# 2211B_SysArrosage_auto.net
KiCad netlist of a schematic drawn in Altium Designer
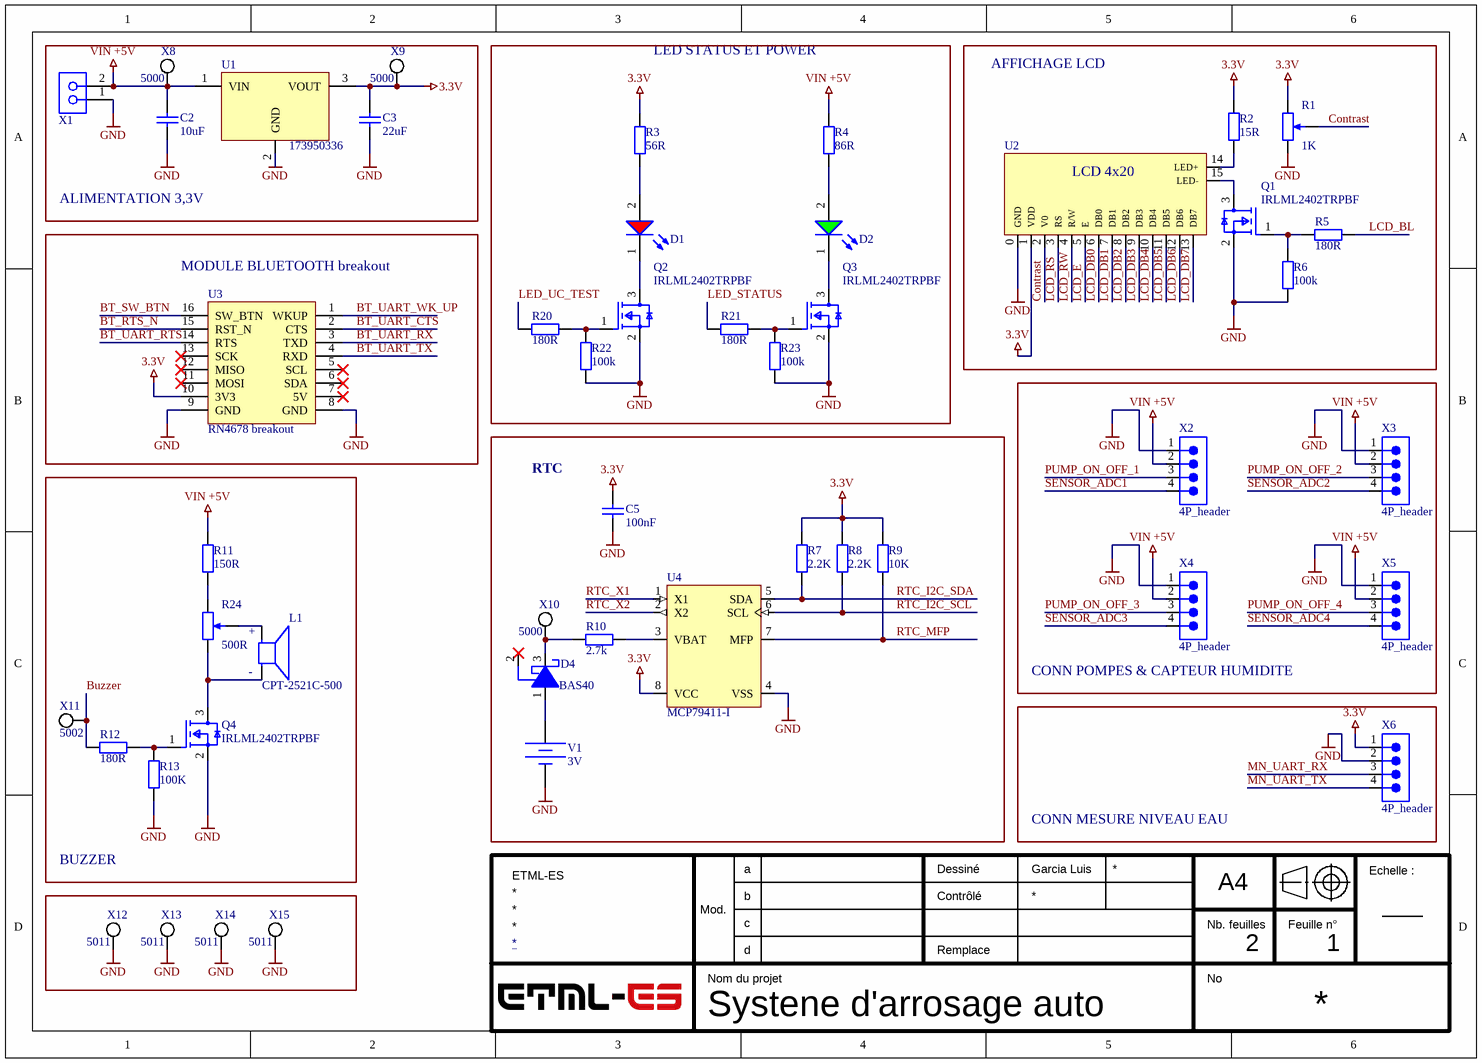
[diagram p0: 2211B_SysArrosage_auto.SchDoc]

(export (version "E")
  (design (tool "Eeschema 10.0.6"))
  (components
    (comp (ref "C2")
      (value "10uF")
      (footprint "CAPC2013X145X48NL20T23")
      (libsource (lib "Sys_Arossage") (part "Capacitor_Non-Polarized"))
    )
    (comp (ref "C3")
      (value "22uF")
      (footprint "CAPC2013X145X48NL20T23")
      (libsource (lib "Sys_Arossage") (part "Capacitor_Non-Polarized"))
    )
    (comp (ref "C5")
      (value "100nF")
      (footprint "CAPC2013X145X48NL20T23")
      (libsource (lib "Sys_Arossage") (part "Capacitor_Non-Polarized"))
    )
    (comp (ref "D1")
      (value "LED_Red_2A-1K")
      (description "LED Uni-Color Hyper Red 640nm 2-Pin Chip LED T/R")
      (fields
        (field (name "MANUFACTURER") "Kingbright")
        (field (name "MANUFACTURER PART NUMBER") "APT2012SECK/J3-PRV")
      )
      (libsource (lib "Optoelectronic") (part "LED_Red_2A-1K"))
    )
    (comp (ref "D2")
      (value "LED_Green_2A-1K")
      (description "LED Uni-Color Green 515nm 2-Pin SMD T/R")
      (fields
        (field (name "MANUFACTURER") "Kingbright")
        (field (name "MANUFACTURER PART NUMBER") "APHCM2012ZGCK-F01")
      )
      (libsource (lib "Optoelectronic") (part "LED_Green_2A-1K"))
    )
    (comp (ref "D4")
      (value "BAS40")
      (footprint "INF-SOT23_M")
      (description "Silicon Schottky Diode, -55 to 150 degC, SOT23, Reel, Green")
      (fields (field (name "MANUFACTURER") "Infineon"))
      (libsource (lib "Sys_Arossage") (part "CMP-1182-00023-1"))
    )
    (comp (ref "L1")
      (value "CPT-2521C-500")
      (description "AUDIO PIEZO TRANSDUCER 50V CHAS")
      (fields (field (name "MANUFACTURER") "CUI Devices"))
      (libsource (lib "Sys_Arossage") (part "Buzzer"))
    )
    (comp (ref "Q1")
      (value "IRLML2402TRPBF")
      (footprint "FP-Micro3-IPC_C")
      (description "MOSFET N-CH 20V 1.2A SOT-23")
      (fields (field (name "MANUFACTURER") "Infineon"))
      (libsource (lib "Sys_Arossage") (part "CMP-32901-000179-1"))
    )
    (comp (ref "Q2")
      (value "IRLML2402TRPBF")
      (footprint "FP-Micro3-IPC_C")
      (description "MOSFET N-CH 20V 1.2A SOT-23")
      (fields (field (name "MANUFACTURER") "Infineon"))
      (libsource (lib "Sys_Arossage") (part "CMP-32901-000179-1"))
    )
    (comp (ref "Q3")
      (value "IRLML2402TRPBF")
      (footprint "FP-Micro3-IPC_C")
      (description "MOSFET N-CH 20V 1.2A SOT-23")
      (fields (field (name "MANUFACTURER") "Infineon"))
      (libsource (lib "Sys_Arossage") (part "CMP-32901-000179-1"))
    )
    (comp (ref "Q4")
      (value "IRLML2402TRPBF")
      (footprint "FP-Micro3-IPC_C")
      (description "MOSFET N-CH 20V 1.2A SOT-23")
      (fields (field (name "MANUFACTURER") "Infineon"))
      (libsource (lib "Sys_Arossage") (part "CMP-32901-000179-1"))
    )
    (comp (ref "R1")
      (value "1K")
      (footprint "TRIM_3362P-1-102LF")
      (description "In a Tube of 50, 1kO Through Hole Trimmer Potentiometer 0.5W Top Adjust Bourns 3362 Series")
      (fields
        (field (name "MANUFACTURER") "Bourns")
        (field (name "MANUFACTURER PART NUMBER") "3362P-1-102LF")
        (field (name "PUBLISHER") "Altium Limited")
      )
      (libsource (lib "Sys_Arossage") (part "RPot"))
    )
    (comp (ref "R2")
      (value "15R")
      (footprint "RC0805N_YAG-M")
      (description "SMD Chip Resistor, 10 kOhm, ± 1%, 125 mW, 0805 [2012 Metric], Thick Film, General Purpose")
      (fields
        (field (name "MANUFACTURER") "Yageo")
        (field (name "MANUFACTURER PART NUMBER") "RC0805FR-0710KL")
      )
      (libsource (lib "") (part "R-SMD_1"))
    )
    (comp (ref "R3")
      (value "56R")
      (footprint "RC0805N_YAG-M")
      (description "SMD Chip Resistor, 10 kOhm, ± 1%, 125 mW, 0805 [2012 Metric], Thick Film, General Purpose")
      (fields
        (field (name "MANUFACTURER") "Yageo")
        (field (name "MANUFACTURER PART NUMBER") "RC0805FR-0710KL")
      )
      (libsource (lib "") (part "R-SMD_1"))
    )
    (comp (ref "R4")
      (value "86R")
      (footprint "RC0805N_YAG-M")
      (description "SMD Chip Resistor, 10 kOhm, ± 1%, 125 mW, 0805 [2012 Metric], Thick Film, General Purpose")
      (fields
        (field (name "MANUFACTURER") "Yageo")
        (field (name "MANUFACTURER PART NUMBER") "RC0805FR-0710KL")
      )
      (libsource (lib "") (part "R-SMD_1"))
    )
    (comp (ref "R5")
      (value "180R")
      (footprint "RC0805N_YAG-M")
      (description "SMD Chip Resistor, 10 kOhm, ± 1%, 125 mW, 0805 [2012 Metric], Thick Film, General Purpose")
      (fields
        (field (name "MANUFACTURER") "Yageo")
        (field (name "MANUFACTURER PART NUMBER") "RC0805FR-0710KL")
      )
      (libsource (lib "Sys_Arossage") (part "R-SMD"))
    )
    (comp (ref "R6")
      (value "100k")
      (footprint "RC0805N_YAG-M")
      (description "SMD Chip Resistor, 10 kOhm, ± 1%, 125 mW, 0805 [2012 Metric], Thick Film, General Purpose")
      (fields
        (field (name "MANUFACTURER") "Yageo")
        (field (name "MANUFACTURER PART NUMBER") "RC0805FR-0710KL")
      )
      (libsource (lib "") (part "R-SMD_1"))
    )
    (comp (ref "R7")
      (value "2.2K")
      (footprint "RC0805N_YAG-M")
      (description "SMD Chip Resistor, 10 kOhm, ± 1%, 125 mW, 0805 [2012 Metric], Thick Film, General Purpose")
      (fields
        (field (name "MANUFACTURER") "Yageo")
        (field (name "MANUFACTURER PART NUMBER") "RC0805FR-0710KL")
      )
      (libsource (lib "") (part "R-SMD_1"))
    )
    (comp (ref "R8")
      (value "2.2K")
      (footprint "RC0805N_YAG-M")
      (description "SMD Chip Resistor, 10 kOhm, ± 1%, 125 mW, 0805 [2012 Metric], Thick Film, General Purpose")
      (fields
        (field (name "MANUFACTURER") "Yageo")
        (field (name "MANUFACTURER PART NUMBER") "RC0805FR-0710KL")
      )
      (libsource (lib "") (part "R-SMD_1"))
    )
    (comp (ref "R9")
      (value "10K")
      (footprint "RC0805N_YAG-M")
      (description "SMD Chip Resistor, 10 kOhm, ± 1%, 125 mW, 0805 [2012 Metric], Thick Film, General Purpose")
      (fields
        (field (name "MANUFACTURER") "Yageo")
        (field (name "MANUFACTURER PART NUMBER") "RC0805FR-0710KL")
      )
      (libsource (lib "") (part "R-SMD_1"))
    )
    (comp (ref "R10")
      (value "2.7k")
      (footprint "RC0805N_YAG-M")
      (description "SMD Chip Resistor, 10 kOhm, ± 1%, 125 mW, 0805 [2012 Metric], Thick Film, General Purpose")
      (fields
        (field (name "MANUFACTURER") "Yageo")
        (field (name "MANUFACTURER PART NUMBER") "RC0805FR-0710KL")
      )
      (libsource (lib "Sys_Arossage") (part "R-SMD"))
    )
    (comp (ref "R11")
      (value "150R")
      (footprint "RC0805N_YAG-M")
      (description "SMD Chip Resistor, 10 kOhm, ± 1%, 125 mW, 0805 [2012 Metric], Thick Film, General Purpose")
      (fields
        (field (name "MANUFACTURER") "Yageo")
        (field (name "MANUFACTURER PART NUMBER") "RC0805FR-0710KL")
      )
      (libsource (lib "") (part "R-SMD_1"))
    )
    (comp (ref "R12")
      (value "180R")
      (footprint "RC0805N_YAG-M")
      (description "SMD Chip Resistor, 10 kOhm, ± 1%, 125 mW, 0805 [2012 Metric], Thick Film, General Purpose")
      (fields
        (field (name "MANUFACTURER") "Yageo")
        (field (name "MANUFACTURER PART NUMBER") "RC0805FR-0710KL")
      )
      (libsource (lib "Sys_Arossage") (part "R-SMD"))
    )
    (comp (ref "R13")
      (value "100K")
      (footprint "RC0805N_YAG-M")
      (description "SMD Chip Resistor, 10 kOhm, ± 1%, 125 mW, 0805 [2012 Metric], Thick Film, General Purpose")
      (fields
        (field (name "MANUFACTURER") "Yageo")
        (field (name "MANUFACTURER PART NUMBER") "RC0805FR-0710KL")
      )
      (libsource (lib "") (part "R-SMD_2"))
    )
    (comp (ref "R20")
      (value "180R")
      (footprint "RC0805N_YAG-M")
      (description "SMD Chip Resistor, 10 kOhm, ± 1%, 125 mW, 0805 [2012 Metric], Thick Film, General Purpose")
      (fields
        (field (name "MANUFACTURER") "Yageo")
        (field (name "MANUFACTURER PART NUMBER") "RC0805FR-0710KL")
      )
      (libsource (lib "Sys_Arossage") (part "R-SMD"))
    )
    (comp (ref "R21")
      (value "180R")
      (footprint "RC0805N_YAG-M")
      (description "SMD Chip Resistor, 10 kOhm, ± 1%, 125 mW, 0805 [2012 Metric], Thick Film, General Purpose")
      (fields
        (field (name "MANUFACTURER") "Yageo")
        (field (name "MANUFACTURER PART NUMBER") "RC0805FR-0710KL")
      )
      (libsource (lib "Sys_Arossage") (part "R-SMD"))
    )
    (comp (ref "R22")
      (value "100k")
      (footprint "RC0805N_YAG-M")
      (description "SMD Chip Resistor, 10 kOhm, ± 1%, 125 mW, 0805 [2012 Metric], Thick Film, General Purpose")
      (fields
        (field (name "MANUFACTURER") "Yageo")
        (field (name "MANUFACTURER PART NUMBER") "RC0805FR-0710KL")
      )
      (libsource (lib "") (part "R-SMD_1"))
    )
    (comp (ref "R23")
      (value "100k")
      (footprint "RC0805N_YAG-M")
      (description "SMD Chip Resistor, 10 kOhm, ± 1%, 125 mW, 0805 [2012 Metric], Thick Film, General Purpose")
      (fields
        (field (name "MANUFACTURER") "Yageo")
        (field (name "MANUFACTURER PART NUMBER") "RC0805FR-0710KL")
      )
      (libsource (lib "") (part "R-SMD_1"))
    )
    (comp (ref "R24")
      (value "500R")
      (footprint "TRIM_3362P-1-102LF")
      (description "In a Tube of 50, 1kO Through Hole Trimmer Potentiometer 0.5W Top Adjust Bourns 3362 Series")
      (fields
        (field (name "MANUFACTURER") "Bourns")
        (field (name "MANUFACTURER PART NUMBER") "3362P-1-102LF")
        (field (name "PUBLISHER") "Altium Limited")
      )
      (libsource (lib "Sys_Arossage") (part "RPot"))
    )
    (comp (ref "U1")
      (value "173950336")
      (footprint "WPME-FDSM_SIP-3_L11.6W7.55H10.16")
      (description "173950336 WPME-FDSM Fixed Step Down Regulator Module")
      (libsource (lib "Altium Content Vault") (part "SIP-3_WPME-FDSM"))
    )
    (comp (ref "U2")
      (value "NHD-0420AZ-FSW-GBW-33V3")
      (description "Character Display STN Transflective 20Char x 4Line 16-Pin")
      (fields (field (name "MANUFACTURER") "Newhaven Display"))
      (libsource (lib "Sys_Arossage") (part "NHD-0420AZ-FSW-GBW-33V3"))
    )
    (comp (ref "U3")
      (value "RN4678 breakout")
      (description "RN4678 Click Bluetooth Communications Module")
      (fields
        (field (name "MANUFACTURER") "mikroElektronika")
        (field (name "MANUFACTURER PART NUMBER") "MIKROE-2545")
      )
      (libsource (lib "Sys_Arossage") (part "RN4678_CLICK_SOCKET"))
    )
    (comp (ref "U4")
      (value "MCP79411-I")
      (footprint "SOIC-SN8_M")
      (description "Real Time Clock Serial 64byte Clock/Calendar/Alarm/Battery Backup Automotive 8-Pin SOIC N Tube")
      (fields
        (field (name "MANUFACTURER") "Microchip")
        (field (name "MANUFACTURER PART NUMBER") "MCP79411-I/SN")
      )
      (libsource (lib "Sys_Arossage") (part "RTC"))
    )
    (comp (ref "V1")
      (value "Pile 3V")
      (description "pile 3V")
      (fields (field (name "DC MAGNITUDE") "3V"))
      (libsource (lib "Simulation Generic Components") (part "Battery"))
    )
    (comp (ref "X1")
      (value "Header 1x2")
      (footprint "691214110002")
      (description "Conn Terminal Block 2 POS 3.5mm Solder ST Thru-Hole 10A Box")
      (fields
        (field (name "MANUFACTURER") "Wurth Electronics")
        (field (name "MANUFACTURER PART NUMBER") "691214110002")
      )
      (libsource (lib "Sys_Arossage") (part "Header 1x2"))
    )
    (comp (ref "X2")
      (value "4P_header")
      (footprint "61300411121")
      (description "THT Vertical Pin Header WR-PHD, Pitch 2.54 mm, Single Row, 4 pins")
      (fields
        (field (name "MANUFACTURER") "Wurth Electronics")
        (field (name "MANUFACTURER PART NUMBER") "61300411121")
      )
      (libsource (lib "Sys_Arossage") (part "4P_header"))
    )
    (comp (ref "X3")
      (value "4P_header")
      (footprint "61300411121")
      (description "THT Vertical Pin Header WR-PHD, Pitch 2.54 mm, Single Row, 4 pins")
      (fields
        (field (name "MANUFACTURER") "Wurth Electronics")
        (field (name "MANUFACTURER PART NUMBER") "61300411121")
      )
      (libsource (lib "Sys_Arossage") (part "4P_header"))
    )
    (comp (ref "X4")
      (value "4P_header")
      (footprint "61300411121")
      (description "THT Vertical Pin Header WR-PHD, Pitch 2.54 mm, Single Row, 4 pins")
      (fields
        (field (name "MANUFACTURER") "Wurth Electronics")
        (field (name "MANUFACTURER PART NUMBER") "61300411121")
      )
      (libsource (lib "Sys_Arossage") (part "4P_header"))
    )
    (comp (ref "X5")
      (value "4P_header")
      (footprint "61300411121")
      (description "THT Vertical Pin Header WR-PHD, Pitch 2.54 mm, Single Row, 4 pins")
      (fields
        (field (name "MANUFACTURER") "Wurth Electronics")
        (field (name "MANUFACTURER PART NUMBER") "61300411121")
      )
      (libsource (lib "Sys_Arossage") (part "4P_header"))
    )
    (comp (ref "X6")
      (value "4P_header")
      (footprint "61300411121")
      (description "THT Vertical Pin Header WR-PHD, Pitch 2.54 mm, Single Row, 4 pins")
      (fields
        (field (name "MANUFACTURER") "Wurth Electronics")
        (field (name "MANUFACTURER PART NUMBER") "61300411121")
      )
      (libsource (lib "Sys_Arossage") (part "4P_header"))
    )
    (comp (ref "X8")
      (value "5000")
      (footprint "Keystone_5000")
      (description "TEST THT MINIATURE RD")
      (fields (field (name "MANUFACTURER") "Keystone"))
      (libsource (lib "ETML-ES") (part "TEST"))
    )
    (comp (ref "X9")
      (value "5000")
      (footprint "Keystone_5000")
      (description "TEST THT MINIATURE RD")
      (fields (field (name "MANUFACTURER") "Keystone"))
      (libsource (lib "ETML-ES") (part "TEST"))
    )
    (comp (ref "X10")
      (value "5000")
      (footprint "Keystone_5000")
      (description "TEST THT MINIATURE RD")
      (fields (field (name "MANUFACTURER") "Keystone"))
      (libsource (lib "ETML-ES") (part "TEST"))
    )
    (comp (ref "X11")
      (value "5002")
      (footprint "Keystone_5002")
      (description "TEST THT MINIATURE WT")
      (fields (field (name "MANUFACTURER") "Keystone"))
      (libsource (lib "ETML-ES") (part "TEST"))
    )
    (comp (ref "X12")
      (value "5011")
      (footprint "Keystone_5011")
      (description "TEST THT MULTIPURPOSE BK")
      (fields (field (name "MANUFACTURER") "Keystone"))
      (libsource (lib "ETML-ES") (part "TEST"))
    )
    (comp (ref "X13")
      (value "5011")
      (footprint "Keystone_5011")
      (description "TEST THT MULTIPURPOSE BK")
      (fields (field (name "MANUFACTURER") "Keystone"))
      (libsource (lib "ETML-ES") (part "TEST"))
    )
    (comp (ref "X14")
      (value "5011")
      (footprint "Keystone_5011")
      (description "TEST THT MULTIPURPOSE BK")
      (fields (field (name "MANUFACTURER") "Keystone"))
      (libsource (lib "ETML-ES") (part "TEST"))
    )
    (comp (ref "X15")
      (value "5011")
      (footprint "Keystone_5011")
      (description "TEST THT MULTIPURPOSE BK")
      (fields (field (name "MANUFACTURER") "Keystone"))
      (libsource (lib "ETML-ES") (part "TEST"))
    )
  )
  (nets
    (net (code "1") (name "/BT_RTS_N") (class "Default")
      (node (ref "U3") (pin "15") (pinfunction "RST_N_15") (pintype "passive"))
    )
    (net (code "2") (name "/BT_SW_BTN") (class "Default")
      (node (ref "U3") (pin "16") (pinfunction "SW_BTN_16") (pintype "passive"))
    )
    (net (code "3") (name "/BT_UART_CTS") (class "Default")
      (node (ref "U3") (pin "2") (pinfunction "CTS_2") (pintype "passive"))
    )
    (net (code "4") (name "/BT_UART_RTS") (class "Default")
      (node (ref "U3") (pin "14") (pinfunction "RTS_14") (pintype "passive"))
    )
    (net (code "5") (name "/BT_UART_RX") (class "Default")
      (node (ref "U3") (pin "3") (pinfunction "TXD_3") (pintype "passive"))
    )
    (net (code "6") (name "/BT_UART_TX") (class "Default")
      (node (ref "U3") (pin "4") (pinfunction "RXD_4") (pintype "passive"))
    )
    (net (code "7") (name "/BT_UART_WK_UP") (class "Default")
      (node (ref "U3") (pin "1") (pinfunction "WKUP_1") (pintype "passive"))
    )
    (net (code "8") (name "/Buzzer") (class "Default")
      (node (ref "R12") (pin "2") (pinfunction "2_2") (pintype "passive"))
      (node (ref "X11") (pin "1") (pinfunction "TP_1") (pintype "passive"))
    )
    (net (code "9") (name "/Contrast") (class "Default")
      (node (ref "R1") (pin "W") (pinfunction "W_W") (pintype "passive"))
      (node (ref "U2") (pin "2") (pinfunction "V0_2") (pintype "passive"))
    )
    (net (code "10") (name "/LCD_BL") (class "Default")
      (node (ref "R5") (pin "1") (pinfunction "1_1") (pintype "passive"))
    )
    (net (code "11") (name "/LCD_DB0") (class "Default")
      (node (ref "U2") (pin "6") (pinfunction "DB0_6") (pintype "passive"))
    )
    (net (code "12") (name "/LCD_DB1") (class "Default")
      (node (ref "U2") (pin "7") (pinfunction "DB1_7") (pintype "passive"))
    )
    (net (code "13") (name "/LCD_DB2") (class "Default")
      (node (ref "U2") (pin "8") (pinfunction "DB2_8") (pintype "passive"))
    )
    (net (code "14") (name "/LCD_DB3") (class "Default")
      (node (ref "U2") (pin "9") (pinfunction "DB3_9") (pintype "passive"))
    )
    (net (code "15") (name "/LCD_DB4") (class "Default")
      (node (ref "U2") (pin "10") (pinfunction "DB4_10") (pintype "passive"))
    )
    (net (code "16") (name "/LCD_DB5") (class "Default")
      (node (ref "U2") (pin "11") (pinfunction "DB5_11") (pintype "passive"))
    )
    (net (code "17") (name "/LCD_DB6") (class "Default")
      (node (ref "U2") (pin "12") (pinfunction "DB6_12") (pintype "passive"))
    )
    (net (code "18") (name "/LCD_DB7") (class "Default")
      (node (ref "U2") (pin "13") (pinfunction "DB7_13") (pintype "passive"))
    )
    (net (code "19") (name "/LCD_E") (class "Default")
      (node (ref "U2") (pin "5") (pinfunction "E_5") (pintype "passive"))
    )
    (net (code "20") (name "/LCD_RS") (class "Default")
      (node (ref "U2") (pin "3") (pinfunction "RS_3") (pintype "passive"))
    )
    (net (code "21") (name "/LCD_RW") (class "Default")
      (node (ref "U2") (pin "4") (pinfunction "R/W_4") (pintype "passive"))
    )
    (net (code "22") (name "/LED_STATUS") (class "Default")
      (node (ref "R21") (pin "2") (pinfunction "2_2") (pintype "passive"))
    )
    (net (code "23") (name "/LED_UC_TEST") (class "Default")
      (node (ref "R20") (pin "2") (pinfunction "2_2") (pintype "passive"))
    )
    (net (code "24") (name "/MN_UART_RX") (class "Default")
      (node (ref "X6") (pin "3") (pinfunction "3_3") (pintype "passive"))
    )
    (net (code "25") (name "/MN_UART_TX") (class "Default")
      (node (ref "X6") (pin "4") (pinfunction "4_4") (pintype "passive"))
    )
    (net (code "26") (name "/PUMP_ON_OFF_1") (class "Default")
      (node (ref "X2") (pin "3") (pinfunction "3_3") (pintype "passive"))
    )
    (net (code "27") (name "/PUMP_ON_OFF_2") (class "Default")
      (node (ref "X3") (pin "3") (pinfunction "3_3") (pintype "passive"))
    )
    (net (code "28") (name "/PUMP_ON_OFF_3") (class "Default")
      (node (ref "X4") (pin "3") (pinfunction "3_3") (pintype "passive"))
    )
    (net (code "29") (name "/PUMP_ON_OFF_4") (class "Default")
      (node (ref "X5") (pin "3") (pinfunction "3_3") (pintype "passive"))
    )
    (net (code "30") (name "/RTC_I2C_SCL") (class "Default")
      (node (ref "R8") (pin "1") (pinfunction "1_1") (pintype "passive"))
      (node (ref "U4") (pin "6") (pinfunction "SCL_6") (pintype "input"))
    )
    (net (code "31") (name "/RTC_I2C_SDA") (class "Default")
      (node (ref "R7") (pin "1") (pinfunction "1_1") (pintype "passive"))
      (node (ref "U4") (pin "5") (pinfunction "SDA_5") (pintype "bidirectional"))
    )
    (net (code "32") (name "/RTC_MFP") (class "Default")
      (node (ref "R9") (pin "1") (pinfunction "1_1") (pintype "passive"))
      (node (ref "U4") (pin "7") (pinfunction "MFP_7") (pintype "open_collector"))
    )
    (net (code "33") (name "/RTC_X1") (class "Default")
      (node (ref "U4") (pin "1") (pinfunction "X1_1") (pintype "input"))
    )
    (net (code "34") (name "/RTC_X2") (class "Default")
      (node (ref "U4") (pin "2") (pinfunction "X2_2") (pintype "output"))
    )
    (net (code "35") (name "/SENSOR_ADC1") (class "Default")
      (node (ref "X2") (pin "4") (pinfunction "4_4") (pintype "passive"))
    )
    (net (code "36") (name "/SENSOR_ADC2") (class "Default")
      (node (ref "X3") (pin "4") (pinfunction "4_4") (pintype "passive"))
    )
    (net (code "37") (name "/SENSOR_ADC3") (class "Default")
      (node (ref "X4") (pin "4") (pinfunction "4_4") (pintype "passive"))
    )
    (net (code "38") (name "/SENSOR_ADC4") (class "Default")
      (node (ref "X5") (pin "4") (pinfunction "4_4") (pintype "passive"))
    )
    (net (code "39") (name "3.3V") (class "Default")
      (node (ref "C3") (pin "2") (pinfunction "2_2") (pintype "passive"))
      (node (ref "C5") (pin "2") (pinfunction "2_2") (pintype "passive"))
      (node (ref "R1") (pin "CW") (pinfunction "+_CW") (pintype "passive"))
      (node (ref "R2") (pin "2") (pinfunction "2_2") (pintype "passive"))
      (node (ref "R3") (pin "2") (pinfunction "2_2") (pintype "passive"))
      (node (ref "R7") (pin "2") (pinfunction "2_2") (pintype "passive"))
      (node (ref "R8") (pin "2") (pinfunction "2_2") (pintype "passive"))
      (node (ref "R9") (pin "2") (pinfunction "2_2") (pintype "passive"))
      (node (ref "U1") (pin "3") (pinfunction "VOUT_3") (pintype "passive"))
      (node (ref "U2") (pin "1") (pinfunction "VDD_1") (pintype "passive"))
      (node (ref "U3") (pin "10") (pinfunction "3V3_10") (pintype "passive"))
      (node (ref "U4") (pin "8") (pinfunction "VCC_8") (pintype "passive"))
      (node (ref "X6") (pin "1") (pinfunction "1_1") (pintype "passive"))
      (node (ref "X9") (pin "1") (pinfunction "TP_1") (pintype "passive"))
    )
    (net (code "40") (name "GND") (class "Default")
      (node (ref "C2") (pin "1") (pinfunction "1_1") (pintype "passive"))
      (node (ref "C3") (pin "1") (pinfunction "1_1") (pintype "passive"))
      (node (ref "C5") (pin "1") (pinfunction "1_1") (pintype "passive"))
      (node (ref "Q1") (pin "2") (pinfunction "S_2") (pintype "passive"))
      (node (ref "Q2") (pin "2") (pinfunction "S_2") (pintype "passive"))
      (node (ref "Q3") (pin "2") (pinfunction "S_2") (pintype "passive"))
      (node (ref "Q4") (pin "2") (pinfunction "S_2") (pintype "passive"))
      (node (ref "R1") (pin "CCW") (pinfunction "-_CCW") (pintype "passive"))
      (node (ref "R13") (pin "2") (pinfunction "2_2") (pintype "passive"))
      (node (ref "R22") (pin "1") (pinfunction "1_1") (pintype "passive"))
      (node (ref "R23") (pin "1") (pinfunction "1_1") (pintype "passive"))
      (node (ref "R6") (pin "1") (pinfunction "1_1") (pintype "passive"))
      (node (ref "U1") (pin "2") (pinfunction "GND_2") (pintype "passive"))
      (node (ref "U2") (pin "0") (pinfunction "GND_0") (pintype "passive"))
      (node (ref "U3") (pin "8") (pinfunction "GND_8") (pintype "passive"))
      (node (ref "U3") (pin "9") (pinfunction "GND_9") (pintype "passive"))
      (node (ref "U4") (pin "4") (pinfunction "VSS_4") (pintype "passive"))
      (node (ref "V1") (pin "2") (pinfunction "2_2") (pintype "passive"))
      (node (ref "X1") (pin "1") (pinfunction "1_1") (pintype "passive"))
      (node (ref "X12") (pin "1") (pinfunction "TP_1") (pintype "passive"))
      (node (ref "X13") (pin "1") (pinfunction "TP_1") (pintype "passive"))
      (node (ref "X14") (pin "1") (pinfunction "TP_1") (pintype "passive"))
      (node (ref "X15") (pin "1") (pinfunction "TP_1") (pintype "passive"))
      (node (ref "X2") (pin "1") (pinfunction "1_1") (pintype "passive"))
      (node (ref "X3") (pin "1") (pinfunction "1_1") (pintype "passive"))
      (node (ref "X4") (pin "1") (pinfunction "1_1") (pintype "passive"))
      (node (ref "X5") (pin "1") (pinfunction "1_1") (pintype "passive"))
      (node (ref "X6") (pin "2") (pinfunction "2_2") (pintype "passive"))
    )
    (net (code "41") (name "Net-(D1-A)") (class "Default")
      (node (ref "D1") (pin "2") (pinfunction "A_2") (pintype "passive"))
      (node (ref "R3") (pin "1") (pinfunction "1_1") (pintype "passive"))
    )
    (net (code "42") (name "Net-(D1-K)") (class "Default")
      (node (ref "D1") (pin "1") (pinfunction "K_1") (pintype "passive"))
      (node (ref "Q2") (pin "3") (pinfunction "D_3") (pintype "passive"))
    )
    (net (code "43") (name "Net-(D2-A)") (class "Default")
      (node (ref "D2") (pin "2") (pinfunction "A_2") (pintype "passive"))
      (node (ref "R4") (pin "1") (pinfunction "1_1") (pintype "passive"))
    )
    (net (code "44") (name "Net-(D2-K)") (class "Default")
      (node (ref "D2") (pin "1") (pinfunction "K_1") (pintype "passive"))
      (node (ref "Q3") (pin "3") (pinfunction "D_3") (pintype "passive"))
    )
    (net (code "45") (name "Net-(D4-A)") (class "Default")
      (node (ref "D4") (pin "1") (pinfunction "A_1") (pintype "passive"))
      (node (ref "V1") (pin "1") (pinfunction "1_1") (pintype "passive"))
    )
    (net (code "46") (name "Net-(D4-K)") (class "Default")
      (node (ref "D4") (pin "3") (pinfunction "K_3") (pintype "passive"))
      (node (ref "R10") (pin "2") (pinfunction "2_2") (pintype "passive"))
      (node (ref "X10") (pin "1") (pinfunction "TP_1") (pintype "passive"))
    )
    (net (code "47") (name "Net-(L1-NEG)") (class "Default")
      (node (ref "L1") (pin "N") (pinfunction "NEG_N") (pintype "passive"))
      (node (ref "Q4") (pin "3") (pinfunction "D_3") (pintype "passive"))
      (node (ref "R24") (pin "CCW") (pinfunction "-_CCW") (pintype "passive"))
    )
    (net (code "48") (name "Net-(L1-POS)") (class "Default")
      (node (ref "L1") (pin "P") (pinfunction "POS_P") (pintype "passive"))
      (node (ref "R24") (pin "W") (pinfunction "W_W") (pintype "passive"))
    )
    (net (code "49") (name "Net-(Q1-D)") (class "Default")
      (node (ref "Q1") (pin "3") (pinfunction "D_3") (pintype "passive"))
      (node (ref "U2") (pin "15") (pinfunction "LED-_15") (pintype "passive"))
    )
    (net (code "50") (name "Net-(Q1-G)") (class "Default")
      (node (ref "Q1") (pin "1") (pinfunction "G_1") (pintype "passive"))
      (node (ref "R5") (pin "2") (pinfunction "2_2") (pintype "passive"))
      (node (ref "R6") (pin "2") (pinfunction "2_2") (pintype "passive"))
    )
    (net (code "51") (name "Net-(Q2-G)") (class "Default")
      (node (ref "Q2") (pin "1") (pinfunction "G_1") (pintype "passive"))
      (node (ref "R20") (pin "1") (pinfunction "1_1") (pintype "passive"))
      (node (ref "R22") (pin "2") (pinfunction "2_2") (pintype "passive"))
    )
    (net (code "52") (name "Net-(Q3-G)") (class "Default")
      (node (ref "Q3") (pin "1") (pinfunction "G_1") (pintype "passive"))
      (node (ref "R21") (pin "1") (pinfunction "1_1") (pintype "passive"))
      (node (ref "R23") (pin "2") (pinfunction "2_2") (pintype "passive"))
    )
    (net (code "53") (name "Net-(Q4-G)") (class "Default")
      (node (ref "Q4") (pin "1") (pinfunction "G_1") (pintype "passive"))
      (node (ref "R12") (pin "1") (pinfunction "1_1") (pintype "passive"))
      (node (ref "R13") (pin "1") (pinfunction "1_1") (pintype "passive"))
    )
    (net (code "54") (name "Net-(R24-+)") (class "Default")
      (node (ref "R11") (pin "1") (pinfunction "1_1") (pintype "passive"))
      (node (ref "R24") (pin "CW") (pinfunction "+_CW") (pintype "passive"))
    )
    (net (code "55") (name "Net-(U2-LED+)") (class "Default")
      (node (ref "R2") (pin "1") (pinfunction "1_1") (pintype "passive"))
      (node (ref "U2") (pin "14") (pinfunction "LED+_14") (pintype "passive"))
    )
    (net (code "56") (name "Net-(U4-VBAT)") (class "Default")
      (node (ref "R10") (pin "1") (pinfunction "1_1") (pintype "passive"))
      (node (ref "U4") (pin "3") (pinfunction "VBAT_3") (pintype "power_in"))
    )
    (net (code "57") (name "VIN +5V") (class "Default")
      (node (ref "C2") (pin "2") (pinfunction "2_2") (pintype "passive"))
      (node (ref "R11") (pin "2") (pinfunction "2_2") (pintype "passive"))
      (node (ref "R4") (pin "2") (pinfunction "2_2") (pintype "passive"))
      (node (ref "U1") (pin "1") (pinfunction "VIN_1") (pintype "passive"))
      (node (ref "X1") (pin "2") (pinfunction "2_2") (pintype "passive"))
      (node (ref "X2") (pin "2") (pinfunction "2_2") (pintype "passive"))
      (node (ref "X3") (pin "2") (pinfunction "2_2") (pintype "passive"))
      (node (ref "X4") (pin "2") (pinfunction "2_2") (pintype "passive"))
      (node (ref "X5") (pin "2") (pinfunction "2_2") (pintype "passive"))
      (node (ref "X8") (pin "1") (pinfunction "TP_1") (pintype "passive"))
    )
    (net (code "58") (name "unconnected-(D4-NC-Pad2)") (class "Default")
      (node (ref "D4") (pin "2") (pinfunction "NC_2") (pintype "passive+no_connect"))
    )
    (net (code "59") (name "unconnected-(U3-5V-Pad7)") (class "Default")
      (node (ref "U3") (pin "7") (pinfunction "5V_7") (pintype "passive+no_connect"))
    )
    (net (code "60") (name "unconnected-(U3-MISO-Pad12)") (class "Default")
      (node (ref "U3") (pin "12") (pinfunction "MISO_12") (pintype "passive+no_connect"))
    )
    (net (code "61") (name "unconnected-(U3-MOSI-Pad11)") (class "Default")
      (node (ref "U3") (pin "11") (pinfunction "MOSI_11") (pintype "passive+no_connect"))
    )
    (net (code "62") (name "unconnected-(U3-SCK-Pad13)") (class "Default")
      (node (ref "U3") (pin "13") (pinfunction "SCK_13") (pintype "passive+no_connect"))
    )
    (net (code "63") (name "unconnected-(U3-SCL-Pad5)") (class "Default")
      (node (ref "U3") (pin "5") (pinfunction "SCL_5") (pintype "passive+no_connect"))
    )
    (net (code "64") (name "unconnected-(U3-SDA-Pad6)") (class "Default")
      (node (ref "U3") (pin "6") (pinfunction "SDA_6") (pintype "passive+no_connect"))
    )
  )
)
